# SCH_plantcare_moisture_module_2025-02-18.net
KiCad netlist of a schematic drawn in EasyEDA
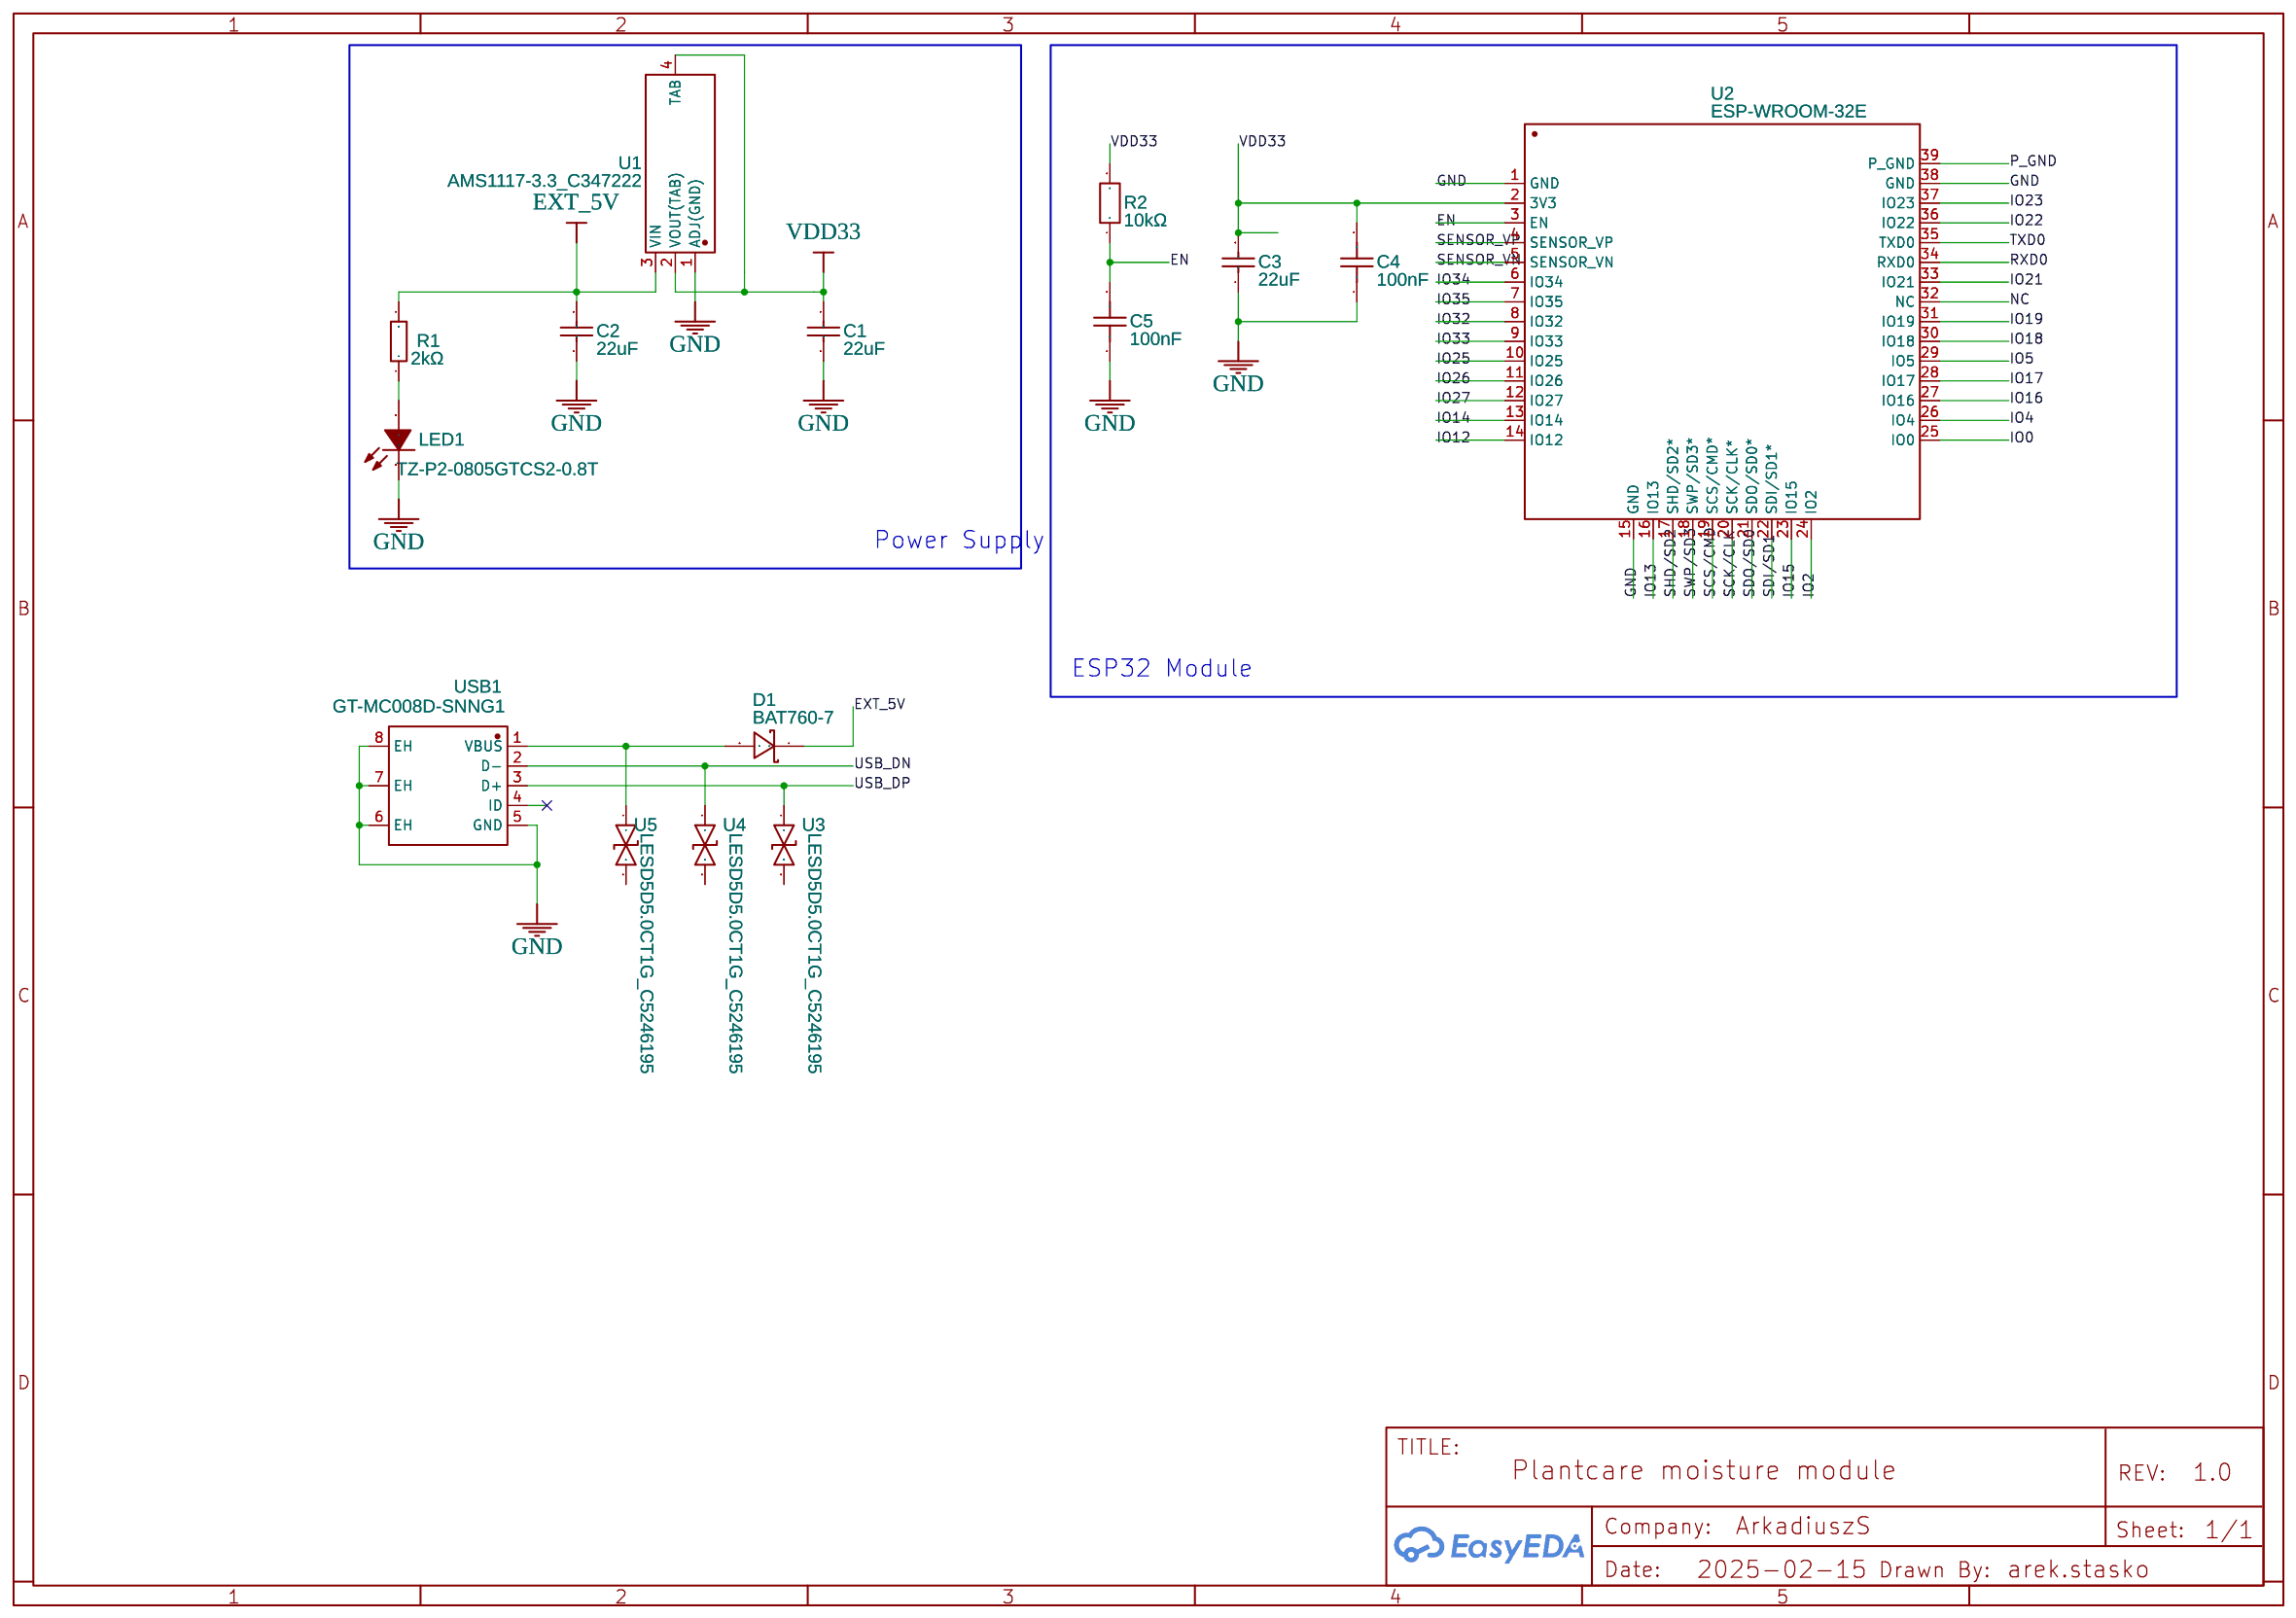
[diagram p0: schematic sheet]

(export (version "E")
  (design (tool "Eeschema 10.0.6"))
  (components
    (comp (ref "C1")
      (value "22uF")
      (fields
        (field (name "Manufacturer Part") "CL21A226MPQNNNE")
        (field (name "Manufacturer") "SAMSUNG(三星)")
      )
      (libsource (lib "") (part "CL21A226MPQNNNE"))
    )
    (comp (ref "C2")
      (value "22uF")
      (fields
        (field (name "Manufacturer Part") "CL21A226MPQNNNE")
        (field (name "Manufacturer") "SAMSUNG(三星)")
      )
      (libsource (lib "") (part "CL21A226MPQNNNE"))
    )
    (comp (ref "C3")
      (value "22uF")
      (fields
        (field (name "Manufacturer Part") "CL21A226MPQNNNE")
        (field (name "Manufacturer") "SAMSUNG(三星)")
      )
      (libsource (lib "") (part "CL21A226MPQNNNE"))
    )
    (comp (ref "C4")
      (value "100nF")
      (fields
        (field (name "Manufacturer Part") "CL10B104KB8NNNC")
        (field (name "Manufacturer") "SAMSUNG(三星)")
      )
      (libsource (lib "") (part "CL10B104KB8NNNC"))
    )
    (comp (ref "C5")
      (value "100nF")
      (fields
        (field (name "Manufacturer Part") "CL10B104KB8NNNC")
        (field (name "Manufacturer") "SAMSUNG(三星)")
      )
      (libsource (lib "") (part "CL10B104KB8NNNC"))
    )
    (comp (ref "D1")
      (value "BAT760-7")
      (fields (field (name "Manufacturer") "DIODES(美台)"))
      (libsource (lib "") (part "BAT760-7"))
    )
    (comp (ref "LED1")
      (value "TZ-P2-0805GTCS2-0.8T")
      (fields (field (name "Manufacturer") "TUOZHAN(拓展光电)"))
      (libsource (lib "") (part "TZ-P2-0805GTCS2-0.8T"))
    )
    (comp (ref "R1")
      (value "2kΩ")
      (fields
        (field (name "Manufacturer Part") "0603WAF2001T5E")
        (field (name "Manufacturer") "UNI-ROYAL(厚声)")
      )
      (libsource (lib "") (part "0603WAF2001T5E"))
    )
    (comp (ref "R2")
      (value "10kΩ")
      (fields (field (name "Manufacturer Part") "FRC0603J103TS") (field (name "Manufacturer") "FOJAN(富捷)"))
      (libsource (lib "") (part "FRC0603J103TS"))
    )
    (comp (ref "U1")
      (value "AMS1117-3.3_C347222")
      (fields (field (name "Manufacturer Part") "AMS1117-3.3") (field (name "Manufacturer") "UMW(友台半导体)"))
      (libsource (lib "") (part "AMS1117-3.3_C347222"))
    )
    (comp (ref "U2")
      (value "ESP-WROOM-32E")
      (fields (field (name "Manufacturer") "DOIT(四博智联)"))
      (libsource (lib "") (part "ESP-WROOM-32E"))
    )
    (comp (ref "U3")
      (value "LESD5D5.0CT1G_C5246195")
      (fields
        (field (name "Manufacturer Part") "LESD5D5.0CT1G")
        (field (name "Manufacturer") "Leiditech(雷卯电子)")
      )
      (libsource (lib "") (part "LESD5D5.0CT1G_C5246195"))
    )
    (comp (ref "U4")
      (value "LESD5D5.0CT1G_C5246195")
      (fields
        (field (name "Manufacturer Part") "LESD5D5.0CT1G")
        (field (name "Manufacturer") "Leiditech(雷卯电子)")
      )
      (libsource (lib "") (part "LESD5D5.0CT1G_C5246195"))
    )
    (comp (ref "U5")
      (value "LESD5D5.0CT1G_C5246195")
      (fields
        (field (name "Manufacturer Part") "LESD5D5.0CT1G")
        (field (name "Manufacturer") "Leiditech(雷卯电子)")
      )
      (libsource (lib "") (part "LESD5D5.0CT1G_C5246195"))
    )
    (comp (ref "USB1")
      (value "GT-MC008D-SNNG1")
      (fields (field (name "Manufacturer") "G-Switch(品赞)"))
      (libsource (lib "") (part "GT-MC008D-SNNG1"))
    )
  )
  (nets
    (net (code "1") (name "/EN") (class "Default")
      (node (ref "C5") (pin "2") (pinfunction "2_2") (pintype "unspecified"))
      (node (ref "R2") (pin "1") (pinfunction "1_1") (pintype "unspecified"))
      (node (ref "U2") (pin "3") (pinfunction "EN_3") (pintype "unspecified"))
    )
    (net (code "2") (name "/IO0") (class "Default")
      (node (ref "U2") (pin "25") (pinfunction "IO0_25") (pintype "unspecified"))
    )
    (net (code "3") (name "/IO2") (class "Default")
      (node (ref "U2") (pin "24") (pinfunction "IO2_24") (pintype "unspecified"))
    )
    (net (code "4") (name "/IO4") (class "Default")
      (node (ref "U2") (pin "26") (pinfunction "IO4_26") (pintype "unspecified"))
    )
    (net (code "5") (name "/IO5") (class "Default")
      (node (ref "U2") (pin "29") (pinfunction "IO5_29") (pintype "unspecified"))
    )
    (net (code "6") (name "/IO12") (class "Default")
      (node (ref "U2") (pin "14") (pinfunction "IO12_14") (pintype "unspecified"))
    )
    (net (code "7") (name "/IO13") (class "Default")
      (node (ref "U2") (pin "16") (pinfunction "IO13_16") (pintype "unspecified"))
    )
    (net (code "8") (name "/IO14") (class "Default")
      (node (ref "U2") (pin "13") (pinfunction "IO14_13") (pintype "unspecified"))
    )
    (net (code "9") (name "/IO15") (class "Default")
      (node (ref "U2") (pin "23") (pinfunction "IO15_23") (pintype "unspecified"))
    )
    (net (code "10") (name "/IO16") (class "Default")
      (node (ref "U2") (pin "27") (pinfunction "IO16_27") (pintype "unspecified"))
    )
    (net (code "11") (name "/IO17") (class "Default")
      (node (ref "U2") (pin "28") (pinfunction "IO17_28") (pintype "unspecified"))
    )
    (net (code "12") (name "/IO18") (class "Default")
      (node (ref "U2") (pin "30") (pinfunction "IO18_30") (pintype "unspecified"))
    )
    (net (code "13") (name "/IO19") (class "Default")
      (node (ref "U2") (pin "31") (pinfunction "IO19_31") (pintype "unspecified"))
    )
    (net (code "14") (name "/IO21") (class "Default")
      (node (ref "U2") (pin "33") (pinfunction "IO21_33") (pintype "unspecified"))
    )
    (net (code "15") (name "/IO22") (class "Default")
      (node (ref "U2") (pin "36") (pinfunction "IO22_36") (pintype "unspecified"))
    )
    (net (code "16") (name "/IO23") (class "Default")
      (node (ref "U2") (pin "37") (pinfunction "IO23_37") (pintype "unspecified"))
    )
    (net (code "17") (name "/IO25") (class "Default")
      (node (ref "U2") (pin "10") (pinfunction "IO25_10") (pintype "unspecified"))
    )
    (net (code "18") (name "/IO26") (class "Default")
      (node (ref "U2") (pin "11") (pinfunction "IO26_11") (pintype "unspecified"))
    )
    (net (code "19") (name "/IO27") (class "Default")
      (node (ref "U2") (pin "12") (pinfunction "IO27_12") (pintype "unspecified"))
    )
    (net (code "20") (name "/IO32") (class "Default")
      (node (ref "U2") (pin "8") (pinfunction "IO32_8") (pintype "unspecified"))
    )
    (net (code "21") (name "/IO33") (class "Default")
      (node (ref "U2") (pin "9") (pinfunction "IO33_9") (pintype "unspecified"))
    )
    (net (code "22") (name "/IO34") (class "Default")
      (node (ref "U2") (pin "6") (pinfunction "IO34_6") (pintype "unspecified"))
    )
    (net (code "23") (name "/IO35") (class "Default")
      (node (ref "U2") (pin "7") (pinfunction "IO35_7") (pintype "unspecified"))
    )
    (net (code "24") (name "/NC") (class "Default")
      (node (ref "U2") (pin "32") (pinfunction "NC_32") (pintype "unspecified"))
    )
    (net (code "25") (name "/P_GND") (class "Default")
      (node (ref "U2") (pin "39") (pinfunction "P_GND_39") (pintype "unspecified"))
    )
    (net (code "26") (name "/RXD0") (class "Default")
      (node (ref "U2") (pin "34") (pinfunction "RXD0_34") (pintype "unspecified"))
    )
    (net (code "27") (name "/SCK{slash}CLK") (class "Default")
      (node (ref "U2") (pin "20") (pinfunction "SCK/CLK*_20") (pintype "unspecified"))
    )
    (net (code "28") (name "/SCS{slash}CMD") (class "Default")
      (node (ref "U2") (pin "19") (pinfunction "SCS/CMD*_19") (pintype "unspecified"))
    )
    (net (code "29") (name "/SDI{slash}SD1") (class "Default")
      (node (ref "U2") (pin "22") (pinfunction "SDI/SD1*_22") (pintype "unspecified"))
    )
    (net (code "30") (name "/SDO{slash}SD0") (class "Default")
      (node (ref "U2") (pin "21") (pinfunction "SDO/SD0*_21") (pintype "unspecified"))
    )
    (net (code "31") (name "/SENSOR_VN") (class "Default")
      (node (ref "U2") (pin "5") (pinfunction "SENSOR_VN_5") (pintype "unspecified"))
    )
    (net (code "32") (name "/SENSOR_VP") (class "Default")
      (node (ref "U2") (pin "4") (pinfunction "SENSOR_VP_4") (pintype "unspecified"))
    )
    (net (code "33") (name "/SHD{slash}SD2") (class "Default")
      (node (ref "U2") (pin "17") (pinfunction "SHD/SD2*_17") (pintype "unspecified"))
    )
    (net (code "34") (name "/SWP{slash}SD3") (class "Default")
      (node (ref "U2") (pin "18") (pinfunction "SWP/SD3*_18") (pintype "unspecified"))
    )
    (net (code "35") (name "/TXD0") (class "Default")
      (node (ref "U2") (pin "35") (pinfunction "TXD0_35") (pintype "unspecified"))
    )
    (net (code "36") (name "/USB_DN") (class "Default")
      (node (ref "U4") (pin "1") (pinfunction "1_1") (pintype "unspecified"))
      (node (ref "USB1") (pin "2") (pinfunction "D-_2") (pintype "unspecified"))
    )
    (net (code "37") (name "/USB_DP") (class "Default")
      (node (ref "U3") (pin "1") (pinfunction "1_1") (pintype "unspecified"))
      (node (ref "USB1") (pin "3") (pinfunction "D+_3") (pintype "unspecified"))
    )
    (net (code "38") (name "EXT_5V") (class "Default")
      (node (ref "C2") (pin "2") (pinfunction "2_2") (pintype "input"))
      (node (ref "D1") (pin "1") (pinfunction "1_1") (pintype "unspecified"))
      (node (ref "R1") (pin "2") (pinfunction "2_2") (pintype "input"))
      (node (ref "U1") (pin "3") (pinfunction "VIN_3") (pintype "unspecified"))
    )
    (net (code "39") (name "GND") (class "Default")
      (node (ref "C1") (pin "1") (pinfunction "1_1") (pintype "input"))
      (node (ref "C2") (pin "1") (pinfunction "1_1") (pintype "input"))
      (node (ref "C3") (pin "1") (pinfunction "1_1") (pintype "input"))
      (node (ref "C4") (pin "1") (pinfunction "1_1") (pintype "unspecified"))
      (node (ref "C5") (pin "1") (pinfunction "1_1") (pintype "unspecified"))
      (node (ref "LED1") (pin "1") (pinfunction "-_1") (pintype "unspecified"))
      (node (ref "U1") (pin "1") (pinfunction "ADJ(GND)_1") (pintype "unspecified"))
      (node (ref "U2") (pin "1") (pinfunction "GND_1") (pintype "unspecified"))
      (node (ref "U2") (pin "15") (pinfunction "GND_15") (pintype "unspecified"))
      (node (ref "U2") (pin "38") (pinfunction "GND_38") (pintype "unspecified"))
      (node (ref "USB1") (pin "5") (pinfunction "GND_5") (pintype "unspecified"))
      (node (ref "USB1") (pin "6") (pinfunction "EH_6") (pintype "unspecified"))
      (node (ref "USB1") (pin "7") (pinfunction "EH_7") (pintype "unspecified"))
      (node (ref "USB1") (pin "8") (pinfunction "EH_8") (pintype "unspecified"))
    )
    (net (code "40") (name "Net-(LED1-+)") (class "Default")
      (node (ref "LED1") (pin "2") (pinfunction "+_2") (pintype "unspecified"))
      (node (ref "R1") (pin "1") (pinfunction "1_1") (pintype "input"))
    )
    (net (code "41") (name "Net-(USB1-VBUS)") (class "Default")
      (node (ref "D1") (pin "2") (pinfunction "2_2") (pintype "unspecified"))
      (node (ref "U5") (pin "1") (pinfunction "1_1") (pintype "unspecified"))
      (node (ref "USB1") (pin "1") (pinfunction "VBUS_1") (pintype "unspecified"))
    )
    (net (code "42") (name "VDD33") (class "Default")
      (node (ref "C1") (pin "2") (pinfunction "2_2") (pintype "input"))
      (node (ref "C3") (pin "2") (pinfunction "2_2") (pintype "input"))
      (node (ref "C4") (pin "2") (pinfunction "2_2") (pintype "unspecified"))
      (node (ref "R2") (pin "2") (pinfunction "2_2") (pintype "unspecified"))
      (node (ref "U1") (pin "2") (pinfunction "VOUT(TAB)_2") (pintype "unspecified"))
      (node (ref "U1") (pin "4") (pinfunction "TAB_4") (pintype "unspecified"))
      (node (ref "U2") (pin "2") (pinfunction "3V3_2") (pintype "unspecified"))
    )
    (net (code "43") (name "unconnected-(U3-Pad2)") (class "Default")
      (node (ref "U3") (pin "2") (pinfunction "2_2") (pintype "unspecified"))
    )
    (net (code "44") (name "unconnected-(U4-Pad2)") (class "Default")
      (node (ref "U4") (pin "2") (pinfunction "2_2") (pintype "unspecified"))
    )
    (net (code "45") (name "unconnected-(U5-Pad2)") (class "Default")
      (node (ref "U5") (pin "2") (pinfunction "2_2") (pintype "unspecified"))
    )
    (net (code "46") (name "unconnected-(USB1-ID-Pad4)") (class "Default")
      (node (ref "USB1") (pin "4") (pinfunction "ID_4") (pintype "unspecified+no_connect"))
    )
  )
)
